# -V3.net
KiCad netlist of a schematic drawn in Altium Designer
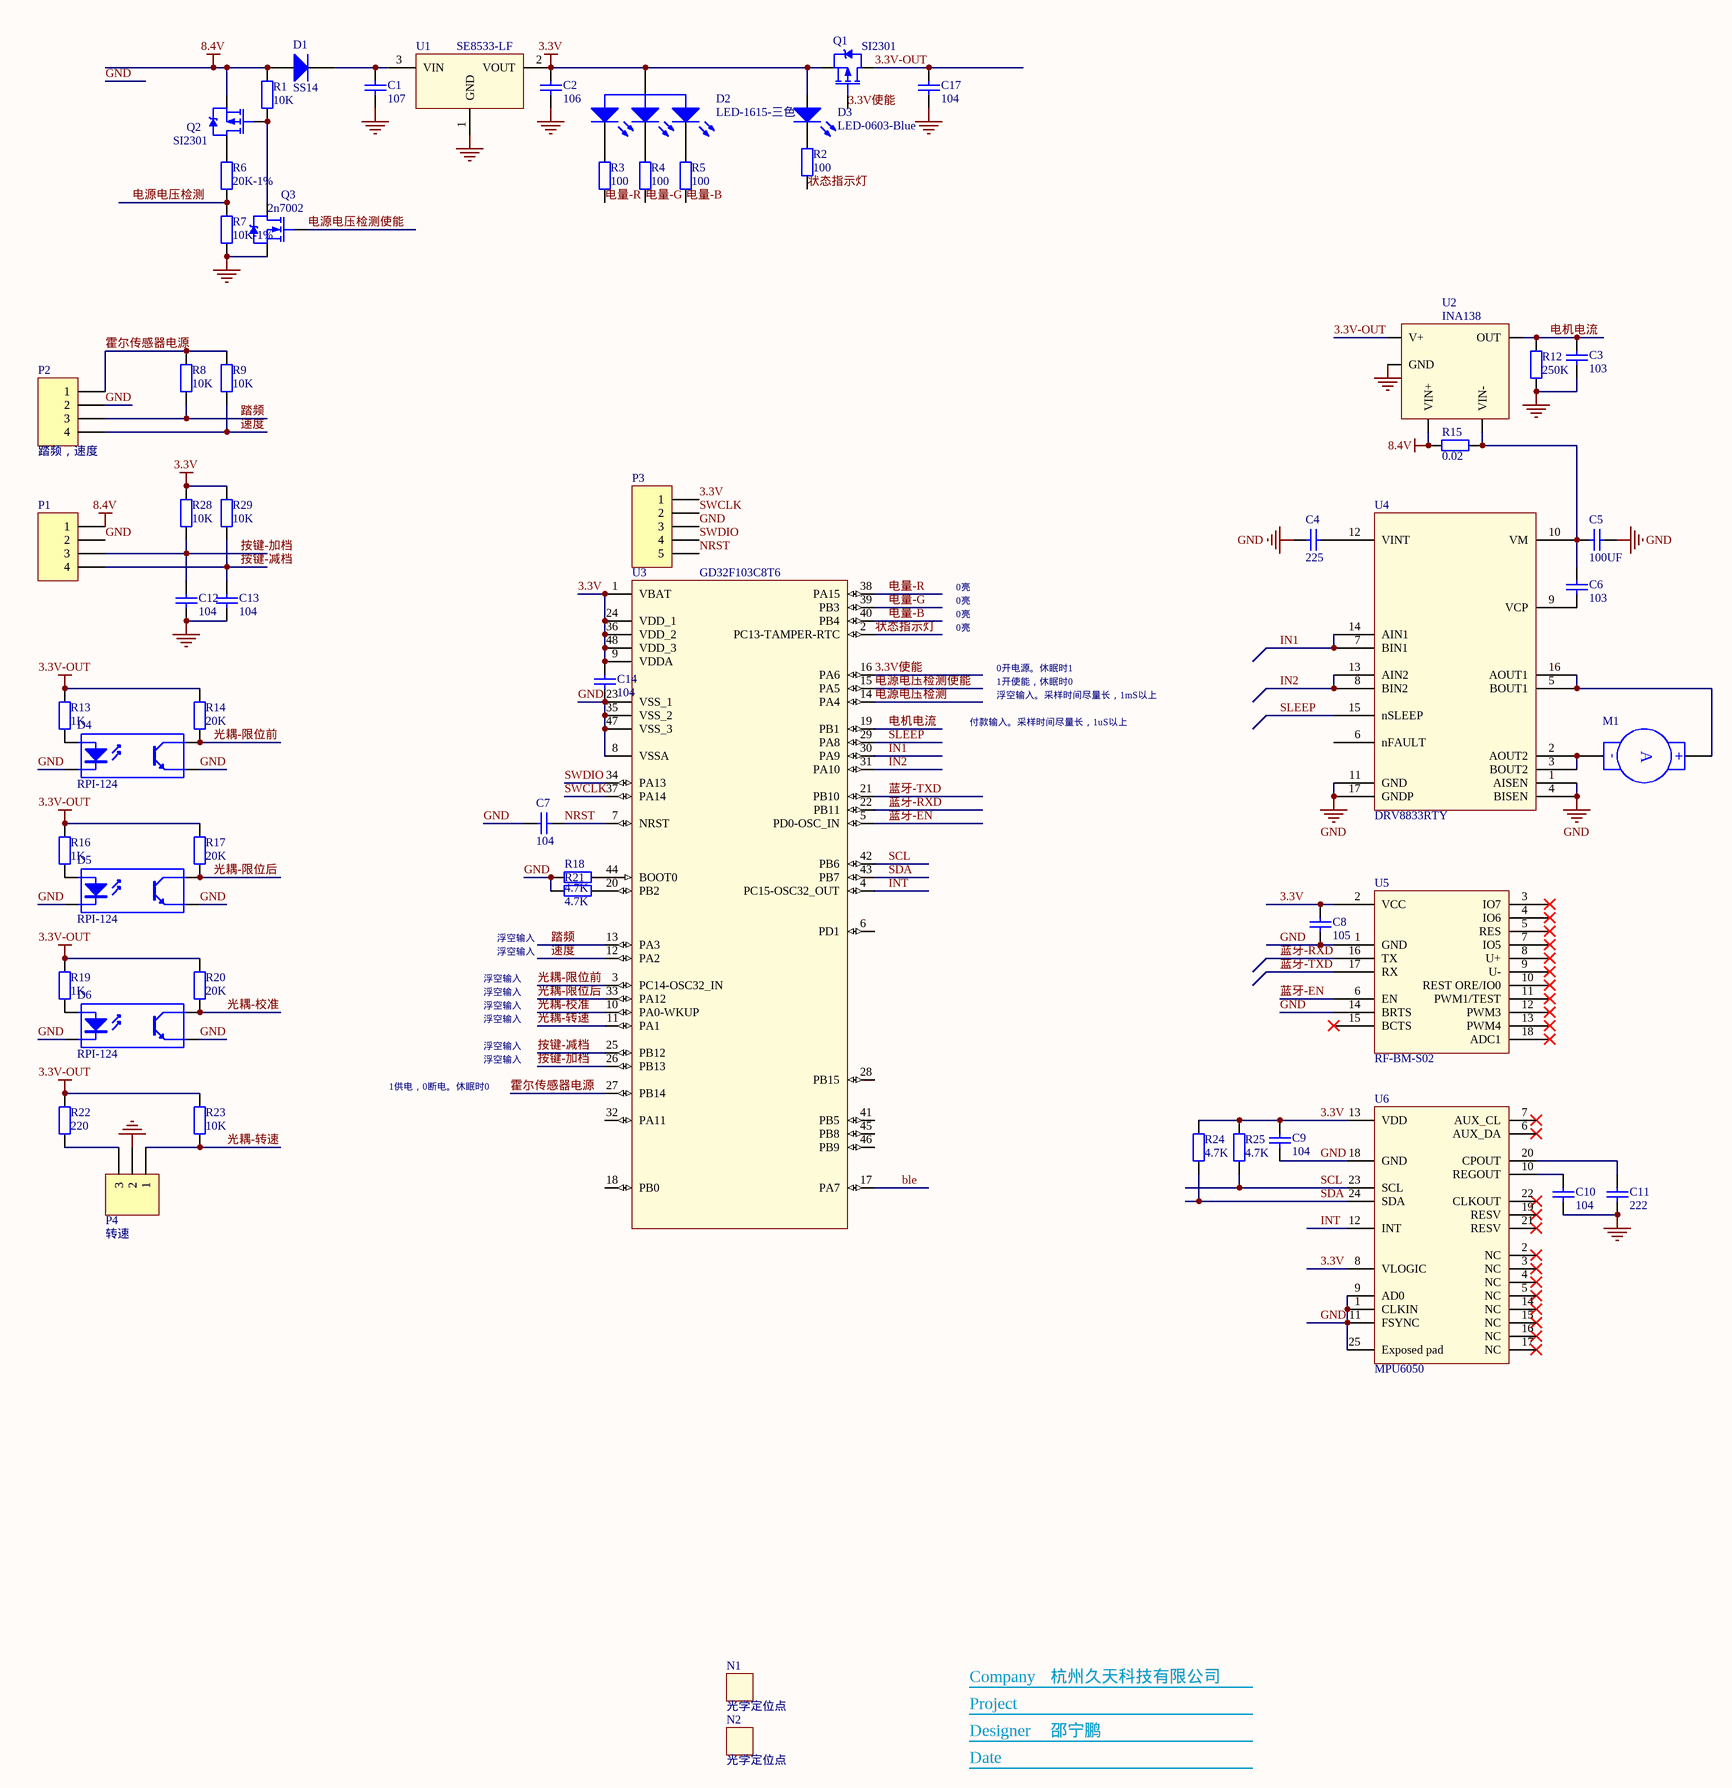
[diagram p0: 拉线式变速器-V3.SchDoc]

(export (version "E")
  (design (tool "Eeschema 10.0.6"))
  (components
    (comp (ref "C1")
      (value "107")
      (footprint "C-1206")
      (description "0805")
      (fields (field (name "PUBLISHER") "Altium Limited"))
      (libsource (lib "2电容-V1.0") (part "Cap-0603"))
    )
    (comp (ref "C2")
      (value "106")
      (footprint "C-0603-M")
      (description "0805")
      (fields (field (name "PUBLISHER") "Altium Limited"))
      (libsource (lib "2电容-V1.0") (part "Cap-0603"))
    )
    (comp (ref "C3")
      (value "103")
      (footprint "C-0603-M")
      (description "0805")
      (fields (field (name "PUBLISHER") "Altium Limited"))
      (libsource (lib "2电容-V1.0") (part "Cap-0603"))
    )
    (comp (ref "C4")
      (value "225")
      (footprint "C-0603-M")
      (description "0805")
      (fields (field (name "PUBLISHER") "Altium Limited"))
      (libsource (lib "2电容-V1.0") (part "Cap-0603"))
    )
    (comp (ref "C5")
      (value "100UF")
      (footprint "C-1206-M")
      (description "0805")
      (fields (field (name "PUBLISHER") "Altium Limited"))
      (libsource (lib "2电容-V1.0") (part "Cap-0805"))
    )
    (comp (ref "C6")
      (value "103")
      (footprint "C-0603-M")
      (description "0805")
      (fields (field (name "PUBLISHER") "Altium Limited"))
      (libsource (lib "2电容-V1.0") (part "Cap-0603"))
    )
    (comp (ref "C7")
      (value "104")
      (footprint "C-0603-M")
      (description "0805")
      (fields (field (name "PUBLISHER") "Altium Limited"))
      (libsource (lib "2电容-V1.0") (part "Cap-0603"))
    )
    (comp (ref "C8")
      (value "105")
      (footprint "C-0603-M")
      (description "0805")
      (fields (field (name "PUBLISHER") "Altium Limited"))
      (libsource (lib "2电容-V1.0") (part "Cap"))
    )
    (comp (ref "C9")
      (value "104")
      (footprint "C-0603-m")
      (description "0805")
      (fields (field (name "PUBLISHER") "Altium Limited"))
      (libsource (lib "2电容-V1.0") (part "Cap-0603"))
    )
    (comp (ref "C10")
      (value "104")
      (footprint "C-0603-m")
      (description "0805")
      (fields (field (name "PUBLISHER") "Altium Limited"))
      (libsource (lib "2电容-V1.0") (part "Cap-0603"))
    )
    (comp (ref "C11")
      (value "222")
      (footprint "C-0603-m")
      (description "0805")
      (fields (field (name "PUBLISHER") "Altium Limited"))
      (libsource (lib "2电容-V1.0") (part "Cap-0603"))
    )
    (comp (ref "C12")
      (value "104")
      (footprint "C-0603-M")
      (description "0805")
      (fields (field (name "PUBLISHER") "Altium Limited"))
      (libsource (lib "2电容-V1.0") (part "Cap-0603"))
    )
    (comp (ref "C13")
      (value "104")
      (footprint "C-0603-M")
      (description "0805")
      (fields (field (name "PUBLISHER") "Altium Limited"))
      (libsource (lib "2电容-V1.0") (part "Cap-0603"))
    )
    (comp (ref "C14")
      (value "104")
      (footprint "C-0603-M")
      (description "0805")
      (fields (field (name "PUBLISHER") "Altium Limited"))
      (libsource (lib "2电容-V1.0") (part "Cap-0603"))
    )
    (comp (ref "C17")
      (value "104")
      (footprint "C-0603-M")
      (description "0805")
      (fields (field (name "PUBLISHER") "Altium Limited"))
      (libsource (lib "2电容-V1.0") (part "Cap-0603"))
    )
    (comp (ref "D1")
      (value "SS14")
      (footprint "D-0603-M")
      (description "SMA")
      (libsource (lib "4二极管-V1.0") (part "SS14"))
    )
    (comp (ref "D2")
      (value "LED-1615-三色")
      (footprint "LED-1615-三色")
      (libsource (lib "4二极管-V1.1") (part "LED-1615-三色"))
    )
    (comp (ref "D3")
      (value "LED-0603-Blue")
      (footprint "LED-0603-Blue")
      (fields (field (name "PUBLISHER") "Altium Limited"))
      (libsource (lib "4二极管-V1.1") (part "LED-0603-Blue"))
    )
    (comp (ref "D4")
      (value "RPI-124")
      (footprint "RPI-124")
      (description "光电")
      (libsource (lib "4二极管-V11") (part "GP1S21"))
    )
    (comp (ref "D5")
      (value "RPI-124")
      (footprint "RPI-124")
      (description "光电")
      (libsource (lib "4二极管-V11") (part "GP1S21"))
    )
    (comp (ref "D6")
      (value "RPI-124")
      (footprint "RPI-124")
      (description "光电")
      (libsource (lib "4二极管-V11") (part "GP1S21"))
    )
    (comp (ref "M1")
      (value "~")
      (footprint "ZH1.5-2P-插件-直针")
      (description "直流电机")
      (fields (field (name "PUBLISHER") "Altium Limited"))
      (libsource (lib "3电感-V1.0") (part "Motor Servo"))
    )
    (comp (ref "N1") (value "光学定位点") (footprint "MARK-1mm-3mm") (libsource (lib "11其他元件-V1.0") (part "无引脚")))
    (comp (ref "N2") (value "光学定位点") (footprint "MARK-1mm-3mm") (libsource (lib "11其他元件-V1.0") (part "无引脚")))
    (comp (ref "P1")
      (value "~")
      (footprint "ZH1.5-4P-插件-直针")
      (description "Header, 4-Pin")
      (fields (field (name "PUBLISHER") "Altium Limited"))
      (libsource (lib "5排针-V1.0") (part "Header 4"))
    )
    (comp (ref "P2")
      (value "踏频，速度")
      (footprint "ZH1.5-4P-插件-直针")
      (description "Header, 4-Pin")
      (fields (field (name "PUBLISHER") "Altium Limited"))
      (libsource (lib "5排针-V1.0") (part "Header 4"))
    )
    (comp (ref "P3")
      (value "~")
      (footprint "5P下载口")
      (description "Header, 5-Pin")
      (fields (field (name "PUBLISHER") "Altium Limited"))
      (libsource (lib "5排针-V1.0") (part "Header 5"))
    )
    (comp (ref "P4")
      (value "转速")
      (footprint "ZH1.5-3P-插件-直针")
      (description "Header, 3-Pin")
      (fields (field (name "PUBLISHER") "Altium Limited"))
      (libsource (lib "5排针-V1.0") (part "Header 3"))
    )
    (comp (ref "Q1")
      (value "SI2301")
      (footprint "SOT-23")
      (description "SOT-23")
      (libsource (lib "4二极管-V1.1") (part "SI2301"))
    )
    (comp (ref "Q2")
      (value "SI2301")
      (footprint "SOT-23")
      (description "SOT-23")
      (libsource (lib "4二极管-V1.1") (part "SI2301"))
    )
    (comp (ref "Q3")
      (value "2n7002")
      (footprint "SOT-23")
      (description "SOT-23")
      (libsource (lib "4二极管-V1.1") (part "SI2300"))
    )
    (comp (ref "R1")
      (value "10K")
      (footprint "R-0603-M")
      (description "0603")
      (fields (field (name "PUBLISHER") "Altium Limited"))
      (libsource (lib "") (part "Res2-0603_2"))
    )
    (comp (ref "R2")
      (value "100")
      (footprint "R-0603-M")
      (description "0603")
      (fields (field (name "PUBLISHER") "Altium Limited"))
      (libsource (lib "1电阻-V1.0") (part "Res2-0603"))
    )
    (comp (ref "R3")
      (value "100")
      (footprint "R-0603-M")
      (description "0603")
      (fields (field (name "PUBLISHER") "Altium Limited"))
      (libsource (lib "1电阻-V1.0") (part "Res2-0603"))
    )
    (comp (ref "R4")
      (value "100")
      (footprint "R-0603-M")
      (description "0603")
      (fields (field (name "PUBLISHER") "Altium Limited"))
      (libsource (lib "1电阻-V1.0") (part "Res2-0603"))
    )
    (comp (ref "R5")
      (value "100")
      (footprint "R-0603-M")
      (description "0603")
      (fields (field (name "PUBLISHER") "Altium Limited"))
      (libsource (lib "1电阻-V1.0") (part "Res2-0603"))
    )
    (comp (ref "R6")
      (value "20K-1%")
      (footprint "R-0603-M")
      (description "0603")
      (fields (field (name "PUBLISHER") "Altium Limited"))
      (libsource (lib "") (part "Res2-0603_2"))
    )
    (comp (ref "R7")
      (value "10K-1%")
      (footprint "R-0603-M")
      (description "0603")
      (fields (field (name "PUBLISHER") "Altium Limited"))
      (libsource (lib "") (part "Res2-0603_2"))
    )
    (comp (ref "R8")
      (value "10K")
      (footprint "R-0603-m")
      (description "0603")
      (fields (field (name "PUBLISHER") "Altium Limited"))
      (libsource (lib "1电阻-V1.0") (part "Res2-0603-"))
    )
    (comp (ref "R9")
      (value "10K")
      (footprint "R-0603-m")
      (description "0603")
      (fields (field (name "PUBLISHER") "Altium Limited"))
      (libsource (lib "1电阻-V1.0") (part "Res2-0603-"))
    )
    (comp (ref "R12")
      (value "250K")
      (footprint "R-0603-m")
      (description "0603")
      (fields (field (name "PUBLISHER") "Altium Limited"))
      (libsource (lib "1电阻-V1.0") (part "Res2-0603"))
    )
    (comp (ref "R13")
      (value "1K")
      (footprint "R-0603-m")
      (description "0603")
      (fields (field (name "PUBLISHER") "Altium Limited"))
      (libsource (lib "1电阻-V1.0") (part "Res2-0603"))
    )
    (comp (ref "R14")
      (value "20K")
      (footprint "R-0603-m")
      (description "0603")
      (fields (field (name "PUBLISHER") "Altium Limited"))
      (libsource (lib "1电阻-V1.0") (part "Res2-0603"))
    )
    (comp (ref "R15")
      (value "0.02")
      (footprint "R-0603-m")
      (description "0603")
      (fields (field (name "PUBLISHER") "Altium Limited"))
      (libsource (lib "") (part "Res2-0603_1"))
    )
    (comp (ref "R16")
      (value "1K")
      (footprint "R-0603-m")
      (description "0603")
      (fields (field (name "PUBLISHER") "Altium Limited"))
      (libsource (lib "1电阻-V1.0") (part "Res2-0603"))
    )
    (comp (ref "R17")
      (value "20K")
      (footprint "R-0603-m")
      (description "0603")
      (fields (field (name "PUBLISHER") "Altium Limited"))
      (libsource (lib "1电阻-V1.0") (part "Res2-0603"))
    )
    (comp (ref "R18")
      (value "4.7K")
      (footprint "R-0603-m")
      (description "0603")
      (fields (field (name "PUBLISHER") "Altium Limited"))
      (libsource (lib "") (part "Res2-0603_1"))
    )
    (comp (ref "R19")
      (value "1K")
      (footprint "R-0603-m")
      (description "0603")
      (fields (field (name "PUBLISHER") "Altium Limited"))
      (libsource (lib "1电阻-V1.0") (part "Res2-0603"))
    )
    (comp (ref "R20")
      (value "20K")
      (footprint "R-0603-m")
      (description "0603")
      (fields (field (name "PUBLISHER") "Altium Limited"))
      (libsource (lib "1电阻-V1.0") (part "Res2-0603"))
    )
    (comp (ref "R21")
      (value "4.7K")
      (footprint "R-0603-m")
      (description "0603")
      (fields (field (name "PUBLISHER") "Altium Limited"))
      (libsource (lib "") (part "Res2-0603_1"))
    )
    (comp (ref "R22")
      (value "220")
      (footprint "R-0603-m")
      (description "0603")
      (fields (field (name "PUBLISHER") "Altium Limited"))
      (libsource (lib "1电阻-V1.0") (part "Res2-0603"))
    )
    (comp (ref "R23")
      (value "10K")
      (footprint "R-0603-m")
      (description "0603")
      (fields (field (name "PUBLISHER") "Altium Limited"))
      (libsource (lib "1电阻-V1.0") (part "Res2-0603"))
    )
    (comp (ref "R24")
      (value "4.7K")
      (footprint "R-0603-M")
      (description "0603")
      (fields (field (name "PUBLISHER") "Altium Limited"))
      (libsource (lib "") (part "Res2-0603-_1"))
    )
    (comp (ref "R25")
      (value "4.7K")
      (footprint "R-0603-M")
      (description "0603")
      (fields (field (name "PUBLISHER") "Altium Limited"))
      (libsource (lib "") (part "Res2-0603-_1"))
    )
    (comp (ref "R28")
      (value "10K")
      (footprint "R-0603-m")
      (description "0603")
      (fields (field (name "PUBLISHER") "Altium Limited"))
      (libsource (lib "1电阻-V1.0") (part "Res2-0603-"))
    )
    (comp (ref "R29")
      (value "10K")
      (footprint "R-0603-m")
      (description "0603")
      (fields (field (name "PUBLISHER") "Altium Limited"))
      (libsource (lib "1电阻-V1.0") (part "Res2-0603-"))
    )
    (comp (ref "U1")
      (value "SE8533-LF")
      (footprint "SOT-23")
      (libsource (lib "电源芯片-线性稳压-V1") (part "SE8533-LF"))
    )
    (comp (ref "U2") (value "INA138") (footprint "SOT-23-5-N") (libsource (lib "放大器和线性器件") (part "INA138")))
    (comp (ref "U3")
      (value "GD32F103C8T6")
      (footprint "LQFP48-L")
      (libsource (lib "9单片机-V1.0") (part "GD32F103C8T6"))
    )
    (comp (ref "U4")
      (value "DRV8833RTY")
      (footprint "QFN-16+1")
      (description "刷式电机驱动芯片")
      (libsource (lib "8集成电路-V11") (part "DRV8833RTY"))
    )
    (comp (ref "U5")
      (value "RF-BM-S02")
      (footprint "RF-BM-S02")
      (libsource (lib "6电路模块-V1.0") (part "RF-BM-S02"))
    )
    (comp (ref "U6")
      (value "MPU6050")
      (footprint "QFN-24")
      (description "三轴陀螺仪加速度传感器")
      (libsource (lib "8集成电路-V1.1") (part "MPU6050"))
    )
  )
  (nets
    (net (code "1") (name "/3.3V使能") (class "Default")
      (node (ref "Q1") (pin "1") (pinfunction "G_1") (pintype "passive"))
      (node (ref "U3") (pin "16") (pinfunction "PA6_16") (pintype "bidirectional"))
    )
    (net (code "2") (name "/IN1") (class "Default")
      (node (ref "U3") (pin "30") (pinfunction "PA9_30") (pintype "bidirectional"))
      (node (ref "U4") (pin "14") (pinfunction "AIN1_14") (pintype "passive"))
      (node (ref "U4") (pin "7") (pinfunction "BIN1_7") (pintype "passive"))
    )
    (net (code "3") (name "/IN2") (class "Default")
      (node (ref "U3") (pin "31") (pinfunction "PA10_31") (pintype "bidirectional"))
      (node (ref "U4") (pin "13") (pinfunction "AIN2_13") (pintype "passive"))
      (node (ref "U4") (pin "8") (pinfunction "BIN2_8") (pintype "passive"))
    )
    (net (code "4") (name "/INT") (class "Default")
      (node (ref "U3") (pin "4") (pinfunction "PC15-OSC32_OUT_4") (pintype "bidirectional"))
      (node (ref "U6") (pin "12") (pinfunction "INT_12") (pintype "passive"))
    )
    (net (code "5") (name "/NRST") (class "Default")
      (node (ref "C7") (pin "2") (pinfunction "2_2") (pintype "passive"))
      (node (ref "P3") (pin "5") (pinfunction "5_5") (pintype "passive"))
      (node (ref "U3") (pin "7") (pinfunction "NRST_7") (pintype "bidirectional"))
    )
    (net (code "6") (name "/SCL") (class "Default")
      (node (ref "R25") (pin "1") (pinfunction "1_1") (pintype "passive"))
      (node (ref "U3") (pin "42") (pinfunction "PB6_42") (pintype "bidirectional"))
      (node (ref "U6") (pin "23") (pinfunction "SCL_23") (pintype "passive"))
    )
    (net (code "7") (name "/SDA") (class "Default")
      (node (ref "R24") (pin "1") (pinfunction "1_1") (pintype "passive"))
      (node (ref "U3") (pin "43") (pinfunction "PB7_43") (pintype "bidirectional"))
      (node (ref "U6") (pin "24") (pinfunction "SDA_24") (pintype "passive"))
    )
    (net (code "8") (name "/SLEEP") (class "Default")
      (node (ref "U3") (pin "29") (pinfunction "PA8_29") (pintype "bidirectional"))
      (node (ref "U4") (pin "15") (pinfunction "nSLEEP_15") (pintype "passive"))
    )
    (net (code "9") (name "/SWCLK") (class "Default")
      (node (ref "P3") (pin "2") (pinfunction "2_2") (pintype "passive"))
      (node (ref "U3") (pin "37") (pinfunction "PA14_37") (pintype "bidirectional"))
    )
    (net (code "10") (name "/SWDIO") (class "Default")
      (node (ref "P3") (pin "4") (pinfunction "4_4") (pintype "passive"))
      (node (ref "U3") (pin "34") (pinfunction "PA13_34") (pintype "bidirectional"))
    )
    (net (code "11") (name "/ble") (class "Default")
      (node (ref "U3") (pin "17") (pinfunction "PA7_17") (pintype "bidirectional"))
    )
    (net (code "12") (name "/光耦-校准") (class "Default")
      (node (ref "D6") (pin "4") (pinfunction "C_4") (pintype "passive"))
      (node (ref "R20") (pin "1") (pinfunction "1_1") (pintype "passive"))
      (node (ref "U3") (pin "10") (pinfunction "PA0-WKUP_10") (pintype "bidirectional"))
    )
    (net (code "13") (name "/光耦-转速") (class "Default")
      (node (ref "P4") (pin "1") (pinfunction "1_1") (pintype "passive"))
      (node (ref "R23") (pin "1") (pinfunction "1_1") (pintype "passive"))
      (node (ref "U3") (pin "11") (pinfunction "PA1_11") (pintype "bidirectional"))
    )
    (net (code "14") (name "/光耦-限位前") (class "Default")
      (node (ref "D4") (pin "4") (pinfunction "C_4") (pintype "passive"))
      (node (ref "R14") (pin "1") (pinfunction "1_1") (pintype "passive"))
      (node (ref "U3") (pin "3") (pinfunction "PC14-OSC32_IN_3") (pintype "bidirectional"))
    )
    (net (code "15") (name "/光耦-限位后") (class "Default")
      (node (ref "D5") (pin "4") (pinfunction "C_4") (pintype "passive"))
      (node (ref "R17") (pin "1") (pinfunction "1_1") (pintype "passive"))
      (node (ref "U3") (pin "33") (pinfunction "PA12_33") (pintype "bidirectional"))
    )
    (net (code "16") (name "/按键-减档") (class "Default")
      (node (ref "C13") (pin "2") (pinfunction "2_2") (pintype "passive"))
      (node (ref "P1") (pin "4") (pinfunction "4_4") (pintype "passive"))
      (node (ref "R29") (pin "2") (pinfunction "2_2") (pintype "passive"))
      (node (ref "U3") (pin "25") (pinfunction "PB12_25") (pintype "bidirectional"))
    )
    (net (code "17") (name "/按键-加档") (class "Default")
      (node (ref "C12") (pin "2") (pinfunction "2_2") (pintype "passive"))
      (node (ref "P1") (pin "3") (pinfunction "3_3") (pintype "passive"))
      (node (ref "R28") (pin "2") (pinfunction "2_2") (pintype "passive"))
      (node (ref "U3") (pin "26") (pinfunction "PB13_26") (pintype "bidirectional"))
    )
    (net (code "18") (name "/状态指示灯") (class "Default")
      (node (ref "R2") (pin "1") (pinfunction "1_1") (pintype "passive"))
      (node (ref "U3") (pin "2") (pinfunction "PC13-TAMPER-RTC_2") (pintype "bidirectional"))
    )
    (net (code "19") (name "/电机电流") (class "Default")
      (node (ref "C3") (pin "1") (pinfunction "1_1") (pintype "passive"))
      (node (ref "R12") (pin "2") (pinfunction "2_2") (pintype "passive"))
      (node (ref "U2") (pin "1") (pinfunction "OUT_1") (pintype "passive"))
      (node (ref "U3") (pin "19") (pinfunction "PB1_19") (pintype "bidirectional"))
    )
    (net (code "20") (name "/电源电压检测") (class "Default")
      (node (ref "R6") (pin "2") (pinfunction "2_2") (pintype "passive"))
      (node (ref "R7") (pin "1") (pinfunction "1_1") (pintype "passive"))
      (node (ref "U3") (pin "14") (pinfunction "PA4_14") (pintype "bidirectional"))
    )
    (net (code "21") (name "/电源电压检测使能") (class "Default")
      (node (ref "Q3") (pin "1") (pinfunction "G_1") (pintype "passive"))
      (node (ref "U3") (pin "15") (pinfunction "PA5_15") (pintype "bidirectional"))
    )
    (net (code "22") (name "/电量-B") (class "Default")
      (node (ref "R5") (pin "1") (pinfunction "1_1") (pintype "passive"))
      (node (ref "U3") (pin "40") (pinfunction "PB4_40") (pintype "bidirectional"))
    )
    (net (code "23") (name "/电量-G") (class "Default")
      (node (ref "R4") (pin "1") (pinfunction "1_1") (pintype "passive"))
      (node (ref "U3") (pin "39") (pinfunction "PB3_39") (pintype "bidirectional"))
    )
    (net (code "24") (name "/电量-R") (class "Default")
      (node (ref "R3") (pin "1") (pinfunction "1_1") (pintype "passive"))
      (node (ref "U3") (pin "38") (pinfunction "PA15_38") (pintype "bidirectional"))
    )
    (net (code "25") (name "/蓝牙-EN") (class "Default")
      (node (ref "U3") (pin "5") (pinfunction "PD0-OSC_IN_5") (pintype "bidirectional"))
      (node (ref "U5") (pin "6") (pinfunction "EN_6") (pintype "passive"))
    )
    (net (code "26") (name "/蓝牙-RXD") (class "Default")
      (node (ref "U3") (pin "22") (pinfunction "PB11_22") (pintype "bidirectional"))
      (node (ref "U5") (pin "16") (pinfunction "TX_16") (pintype "passive"))
    )
    (net (code "27") (name "/蓝牙-TXD") (class "Default")
      (node (ref "U3") (pin "21") (pinfunction "PB10_21") (pintype "bidirectional"))
      (node (ref "U5") (pin "17") (pinfunction "RX_17") (pintype "passive"))
    )
    (net (code "28") (name "/踏频") (class "Default")
      (node (ref "P2") (pin "3") (pinfunction "3_3") (pintype "passive"))
      (node (ref "R8") (pin "2") (pinfunction "2_2") (pintype "passive"))
      (node (ref "U3") (pin "13") (pinfunction "PA3_13") (pintype "bidirectional"))
    )
    (net (code "29") (name "/速度") (class "Default")
      (node (ref "P2") (pin "4") (pinfunction "4_4") (pintype "passive"))
      (node (ref "R9") (pin "2") (pinfunction "2_2") (pintype "passive"))
      (node (ref "U3") (pin "12") (pinfunction "PA2_12") (pintype "bidirectional"))
    )
    (net (code "30") (name "/霍尔传感器电源") (class "Default")
      (node (ref "P2") (pin "1") (pinfunction "1_1") (pintype "passive"))
      (node (ref "R8") (pin "1") (pinfunction "1_1") (pintype "passive"))
      (node (ref "R9") (pin "1") (pinfunction "1_1") (pintype "passive"))
      (node (ref "U3") (pin "27") (pinfunction "PB14_27") (pintype "bidirectional"))
    )
    (net (code "31") (name "3.3V") (class "Default")
      (node (ref "C14") (pin "1") (pinfunction "1_1") (pintype "passive"))
      (node (ref "C2") (pin "2") (pinfunction "2_2") (pintype "passive"))
      (node (ref "C8") (pin "1") (pinfunction "1_1") (pintype "passive"))
      (node (ref "C9") (pin "1") (pinfunction "1_1") (pintype "passive"))
      (node (ref "D2") (pin "2") (pinfunction "A_2") (pintype "passive"))
      (node (ref "D3") (pin "1") (pinfunction "A_1") (pintype "passive"))
      (node (ref "P3") (pin "1") (pinfunction "1_1") (pintype "passive"))
      (node (ref "Q1") (pin "2") (pinfunction "S_2") (pintype "passive"))
      (node (ref "R24") (pin "2") (pinfunction "2_2") (pintype "passive"))
      (node (ref "R25") (pin "2") (pinfunction "2_2") (pintype "passive"))
      (node (ref "R28") (pin "1") (pinfunction "1_1") (pintype "passive"))
      (node (ref "R29") (pin "1") (pinfunction "1_1") (pintype "passive"))
      (node (ref "U1") (pin "2") (pinfunction "VOUT_2") (pintype "passive"))
      (node (ref "U3") (pin "1") (pinfunction "VBAT_1") (pintype "power_in"))
      (node (ref "U3") (pin "24") (pinfunction "VDD_1_24") (pintype "power_in"))
      (node (ref "U3") (pin "36") (pinfunction "VDD_2_36") (pintype "power_in"))
      (node (ref "U3") (pin "48") (pinfunction "VDD_3_48") (pintype "power_in"))
      (node (ref "U3") (pin "9") (pinfunction "VDDA_9") (pintype "power_in"))
      (node (ref "U5") (pin "2") (pinfunction "VCC_2") (pintype "passive"))
      (node (ref "U6") (pin "13") (pinfunction "VDD_13") (pintype "passive"))
      (node (ref "U6") (pin "8") (pinfunction "VLOGIC_8") (pintype "passive"))
    )
    (net (code "32") (name "3.3V-OUT") (class "Default")
      (node (ref "C17") (pin "1") (pinfunction "1_1") (pintype "passive"))
      (node (ref "Q1") (pin "3") (pinfunction "D_3") (pintype "passive"))
      (node (ref "R13") (pin "2") (pinfunction "2_2") (pintype "passive"))
      (node (ref "R14") (pin "2") (pinfunction "2_2") (pintype "passive"))
      (node (ref "R16") (pin "2") (pinfunction "2_2") (pintype "passive"))
      (node (ref "R17") (pin "2") (pinfunction "2_2") (pintype "passive"))
      (node (ref "R19") (pin "2") (pinfunction "2_2") (pintype "passive"))
      (node (ref "R20") (pin "2") (pinfunction "2_2") (pintype "passive"))
      (node (ref "R22") (pin "2") (pinfunction "2_2") (pintype "passive"))
      (node (ref "R23") (pin "2") (pinfunction "2_2") (pintype "passive"))
      (node (ref "U2") (pin "5") (pinfunction "V+_5") (pintype "passive"))
    )
    (net (code "33") (name "8.4V") (class "Default")
      (node (ref "D1") (pin "1") (pinfunction "A_1") (pintype "passive"))
      (node (ref "P1") (pin "1") (pinfunction "1_1") (pintype "passive"))
      (node (ref "Q2") (pin "2") (pinfunction "S_2") (pintype "passive"))
      (node (ref "R1") (pin "1") (pinfunction "1_1") (pintype "passive"))
      (node (ref "R15") (pin "2") (pinfunction "2_2") (pintype "passive"))
      (node (ref "U2") (pin "3") (pinfunction "VIN+_3") (pintype "passive"))
    )
    (net (code "34") (name "GND") (class "Default")
      (node (ref "C1") (pin "1") (pinfunction "1_1") (pintype "passive"))
      (node (ref "C10") (pin "2") (pinfunction "2_2") (pintype "passive"))
      (node (ref "C11") (pin "2") (pinfunction "2_2") (pintype "passive"))
      (node (ref "C12") (pin "1") (pinfunction "1_1") (pintype "passive"))
      (node (ref "C13") (pin "1") (pinfunction "1_1") (pintype "passive"))
      (node (ref "C14") (pin "2") (pinfunction "2_2") (pintype "passive"))
      (node (ref "C17") (pin "2") (pinfunction "2_2") (pintype "passive"))
      (node (ref "C2") (pin "1") (pinfunction "1_1") (pintype "passive"))
      (node (ref "C3") (pin "2") (pinfunction "2_2") (pintype "passive"))
      (node (ref "C4") (pin "1") (pinfunction "1_1") (pintype "passive"))
      (node (ref "C5") (pin "1") (pinfunction "1_1") (pintype "passive"))
      (node (ref "C7") (pin "1") (pinfunction "1_1") (pintype "passive"))
      (node (ref "C8") (pin "2") (pinfunction "2_2") (pintype "passive"))
      (node (ref "C9") (pin "2") (pinfunction "2_2") (pintype "passive"))
      (node (ref "D4") (pin "2") (pinfunction "K_2") (pintype "passive"))
      (node (ref "D4") (pin "3") (pinfunction "E_3") (pintype "passive"))
      (node (ref "D5") (pin "2") (pinfunction "K_2") (pintype "passive"))
      (node (ref "D5") (pin "3") (pinfunction "E_3") (pintype "passive"))
      (node (ref "D6") (pin "2") (pinfunction "K_2") (pintype "passive"))
      (node (ref "D6") (pin "3") (pinfunction "E_3") (pintype "passive"))
      (node (ref "P1") (pin "2") (pinfunction "2_2") (pintype "passive"))
      (node (ref "P2") (pin "2") (pinfunction "2_2") (pintype "passive"))
      (node (ref "P3") (pin "3") (pinfunction "3_3") (pintype "passive"))
      (node (ref "P4") (pin "2") (pinfunction "2_2") (pintype "passive"))
      (node (ref "Q3") (pin "2") (pinfunction "S_2") (pintype "passive"))
      (node (ref "R12") (pin "1") (pinfunction "1_1") (pintype "passive"))
      (node (ref "R18") (pin "2") (pinfunction "2_2") (pintype "passive"))
      (node (ref "R21") (pin "2") (pinfunction "2_2") (pintype "passive"))
      (node (ref "R7") (pin "2") (pinfunction "2_2") (pintype "passive"))
      (node (ref "U1") (pin "1") (pinfunction "GND_1") (pintype "passive"))
      (node (ref "U2") (pin "2") (pinfunction "GND_2") (pintype "passive"))
      (node (ref "U3") (pin "23") (pinfunction "VSS_1_23") (pintype "power_in"))
      (node (ref "U3") (pin "35") (pinfunction "VSS_2_35") (pintype "power_in"))
      (node (ref "U3") (pin "47") (pinfunction "VSS_3_47") (pintype "power_in"))
      (node (ref "U3") (pin "8") (pinfunction "VSSA_8") (pintype "power_in"))
      (node (ref "U4") (pin "1") (pinfunction "AISEN_1") (pintype "passive"))
      (node (ref "U4") (pin "11") (pinfunction "GND_11") (pintype "passive"))
      (node (ref "U4") (pin "17") (pinfunction "GNDP_17") (pintype "passive"))
      (node (ref "U4") (pin "4") (pinfunction "BISEN_4") (pintype "passive"))
      (node (ref "U5") (pin "1") (pinfunction "GND_1") (pintype "passive"))
      (node (ref "U5") (pin "14") (pinfunction "BRTS_14") (pintype "passive"))
      (node (ref "U6") (pin "1") (pinfunction "CLKIN_1") (pintype "passive"))
      (node (ref "U6") (pin "11") (pinfunction "FSYNC_11") (pintype "passive"))
      (node (ref "U6") (pin "18") (pinfunction "GND_18") (pintype "passive"))
      (node (ref "U6") (pin "25") (pinfunction "Exposed_pad_25") (pintype "passive"))
      (node (ref "U6") (pin "9") (pinfunction "AD0_9") (pintype "passive"))
    )
    (net (code "35") (name "Net-(D1-K)") (class "Default")
      (node (ref "C1") (pin "2") (pinfunction "2_2") (pintype "passive"))
      (node (ref "D1") (pin "2") (pinfunction "K_2") (pintype "passive"))
      (node (ref "U1") (pin "3") (pinfunction "VIN_3") (pintype "passive"))
    )
    (net (code "36") (name "Net-(D2-B)") (class "Default")
      (node (ref "D2") (pin "3") (pinfunction "B_3") (pintype "passive"))
      (node (ref "R5") (pin "2") (pinfunction "2_2") (pintype "passive"))
    )
    (net (code "37") (name "Net-(D2-G)") (class "Default")
      (node (ref "D2") (pin "4") (pinfunction "G_4") (pintype "passive"))
      (node (ref "R4") (pin "2") (pinfunction "2_2") (pintype "passive"))
    )
    (net (code "38") (name "Net-(D2-R)") (class "Default")
      (node (ref "D2") (pin "1") (pinfunction "R_1") (pintype "passive"))
      (node (ref "R3") (pin "2") (pinfunction "2_2") (pintype "passive"))
    )
    (net (code "39") (name "Net-(D3-K)") (class "Default")
      (node (ref "D3") (pin "2") (pinfunction "K_2") (pintype "passive"))
      (node (ref "R2") (pin "2") (pinfunction "2_2") (pintype "passive"))
    )
    (net (code "40") (name "Net-(D4-A)") (class "Default")
      (node (ref "D4") (pin "1") (pinfunction "A_1") (pintype "passive"))
      (node (ref "R13") (pin "1") (pinfunction "1_1") (pintype "passive"))
    )
    (net (code "41") (name "Net-(D5-A)") (class "Default")
      (node (ref "D5") (pin "1") (pinfunction "A_1") (pintype "passive"))
      (node (ref "R16") (pin "1") (pinfunction "1_1") (pintype "passive"))
    )
    (net (code "42") (name "Net-(D6-A)") (class "Default")
      (node (ref "D6") (pin "1") (pinfunction "A_1") (pintype "passive"))
      (node (ref "R19") (pin "1") (pinfunction "1_1") (pintype "passive"))
    )
    (net (code "43") (name "Net-(M1-+)") (class "Default")
      (node (ref "M1") (pin "1") (pinfunction "+_1") (pintype "passive"))
      (node (ref "U4") (pin "16") (pinfunction "AOUT1_16") (pintype "passive"))
      (node (ref "U4") (pin "5") (pinfunction "BOUT1_5") (pintype "passive"))
    )
    (net (code "44") (name "Net-(M1--)") (class "Default")
      (node (ref "M1") (pin "2") (pinfunction "-_2") (pintype "passive"))
      (node (ref "U4") (pin "2") (pinfunction "AOUT2_2") (pintype "passive"))
      (node (ref "U4") (pin "3") (pinfunction "BOUT2_3") (pintype "passive"))
    )
    (net (code "45") (name "Net-(P4-Pad3)") (class "Default")
      (node (ref "P4") (pin "3") (pinfunction "3_3") (pintype "passive"))
      (node (ref "R22") (pin "1") (pinfunction "1_1") (pintype "passive"))
    )
    (net (code "46") (name "Net-(Q2-D)") (class "Default")
      (node (ref "Q2") (pin "3") (pinfunction "D_3") (pintype "passive"))
      (node (ref "R6") (pin "1") (pinfunction "1_1") (pintype "passive"))
    )
    (net (code "47") (name "Net-(Q2-G)") (class "Default")
      (node (ref "Q2") (pin "1") (pinfunction "G_1") (pintype "passive"))
      (node (ref "Q3") (pin "3") (pinfunction "D_3") (pintype "passive"))
      (node (ref "R1") (pin "2") (pinfunction "2_2") (pintype "passive"))
    )
    (net (code "48") (name "Net-(U2-VIN-)") (class "Default")
      (node (ref "C5") (pin "2") (pinfunction "2_2") (pintype "passive"))
      (node (ref "C6") (pin "1") (pinfunction "1_1") (pintype "passive"))
      (node (ref "R15") (pin "1") (pinfunction "1_1") (pintype "passive"))
      (node (ref "U2") (pin "4") (pinfunction "VIN-_4") (pintype "passive"))
      (node (ref "U4") (pin "10") (pinfunction "VM_10") (pintype "passive"))
    )
    (net (code "49") (name "Net-(U3-BOOT0)") (class "Default")
      (node (ref "R18") (pin "1") (pinfunction "1_1") (pintype "passive"))
      (node (ref "U3") (pin "44") (pinfunction "BOOT0_44") (pintype "input"))
    )
    (net (code "50") (name "Net-(U3-PB2)") (class "Default")
      (node (ref "R21") (pin "1") (pinfunction "1_1") (pintype "passive"))
      (node (ref "U3") (pin "20") (pinfunction "PB2_20") (pintype "bidirectional"))
    )
    (net (code "51") (name "Net-(U4-VCP)") (class "Default")
      (node (ref "C6") (pin "2") (pinfunction "2_2") (pintype "passive"))
      (node (ref "U4") (pin "9") (pinfunction "VCP_9") (pintype "passive"))
    )
    (net (code "52") (name "Net-(U4-VINT)") (class "Default")
      (node (ref "C4") (pin "2") (pinfunction "2_2") (pintype "passive"))
      (node (ref "U4") (pin "12") (pinfunction "VINT_12") (pintype "passive"))
    )
    (net (code "53") (name "Net-(U6-CPOUT)") (class "Default")
      (node (ref "C11") (pin "1") (pinfunction "1_1") (pintype "passive"))
      (node (ref "U6") (pin "20") (pinfunction "CPOUT_20") (pintype "passive"))
    )
    (net (code "54") (name "Net-(U6-REGOUT)") (class "Default")
      (node (ref "C10") (pin "1") (pinfunction "1_1") (pintype "passive"))
      (node (ref "U6") (pin "10") (pinfunction "REGOUT_10") (pintype "passive"))
    )
    (net (code "55") (name "unconnected-(U3-PA11-Pad32)") (class "Default")
      (node (ref "U3") (pin "32") (pinfunction "PA11_32") (pintype "bidirectional"))
    )
    (net (code "56") (name "unconnected-(U3-PB0-Pad18)") (class "Default")
      (node (ref "U3") (pin "18") (pinfunction "PB0_18") (pintype "bidirectional"))
    )
    (net (code "57") (name "unconnected-(U3-PB5-Pad41)") (class "Default")
      (node (ref "U3") (pin "41") (pinfunction "PB5_41") (pintype "bidirectional"))
    )
    (net (code "58") (name "unconnected-(U3-PB8-Pad45)") (class "Default")
      (node (ref "U3") (pin "45") (pinfunction "PB8_45") (pintype "bidirectional"))
    )
    (net (code "59") (name "unconnected-(U3-PB9-Pad46)") (class "Default")
      (node (ref "U3") (pin "46") (pinfunction "PB9_46") (pintype "bidirectional"))
    )
    (net (code "60") (name "unconnected-(U3-PB15-Pad28)") (class "Default")
      (node (ref "U3") (pin "28") (pinfunction "PB15_28") (pintype "bidirectional"))
    )
    (net (code "61") (name "unconnected-(U3-PD1-Pad6)") (class "Default")
      (node (ref "U3") (pin "6") (pinfunction "PD1_6") (pintype "bidirectional"))
    )
    (net (code "62") (name "unconnected-(U4-nFAULT-Pad6)") (class "Default")
      (node (ref "U4") (pin "6") (pinfunction "nFAULT_6") (pintype "passive"))
    )
    (net (code "63") (name "unconnected-(U5-ADC1-Pad18)") (class "Default")
      (node (ref "U5") (pin "18") (pinfunction "ADC1_18") (pintype "passive+no_connect"))
    )
    (net (code "64") (name "unconnected-(U5-BCTS-Pad15)") (class "Default")
      (node (ref "U5") (pin "15") (pinfunction "BCTS_15") (pintype "passive+no_connect"))
    )
    (net (code "65") (name "unconnected-(U5-IO5-Pad7)") (class "Default")
      (node (ref "U5") (pin "7") (pinfunction "IO5_7") (pintype "passive+no_connect"))
    )
    (net (code "66") (name "unconnected-(U5-IO6-Pad4)") (class "Default")
      (node (ref "U5") (pin "4") (pinfunction "IO6_4") (pintype "passive+no_connect"))
    )
    (net (code "67") (name "unconnected-(U5-IO7-Pad3)") (class "Default")
      (node (ref "U5") (pin "3") (pinfunction "IO7_3") (pintype "passive+no_connect"))
    )
    (net (code "68") (name "unconnected-(U5-PWM1{slash}TEST-Pad11)") (class "Default")
      (node (ref "U5") (pin "11") (pinfunction "PWM1/TEST_11") (pintype "passive+no_connect"))
    )
    (net (code "69") (name "unconnected-(U5-PWM3-Pad12)") (class "Default")
      (node (ref "U5") (pin "12") (pinfunction "PWM3_12") (pintype "passive+no_connect"))
    )
    (net (code "70") (name "unconnected-(U5-PWM4-Pad13)") (class "Default")
      (node (ref "U5") (pin "13") (pinfunction "PWM4_13") (pintype "passive+no_connect"))
    )
    (net (code "71") (name "unconnected-(U5-RES-Pad5)") (class "Default")
      (node (ref "U5") (pin "5") (pinfunction "RES_5") (pintype "passive+no_connect"))
    )
    (net (code "72") (name "unconnected-(U5-REST_ORE{slash}IO0-Pad10)") (class "Default")
      (node (ref "U5") (pin "10") (pinfunction "REST_ORE/IO0_10") (pintype "passive+no_connect"))
    )
    (net (code "73") (name "unconnected-(U5-U+-Pad8)") (class "Default")
      (node (ref "U5") (pin "8") (pinfunction "U+_8") (pintype "passive+no_connect"))
    )
    (net (code "74") (name "unconnected-(U5-U--Pad9)") (class "Default")
      (node (ref "U5") (pin "9") (pinfunction "U-_9") (pintype "passive+no_connect"))
    )
    (net (code "75") (name "unconnected-(U6-AUX_CL-Pad7)") (class "Default")
      (node (ref "U6") (pin "7") (pinfunction "AUX_CL_7") (pintype "passive+no_connect"))
    )
    (net (code "76") (name "unconnected-(U6-AUX_DA-Pad6)") (class "Default")
      (node (ref "U6") (pin "6") (pinfunction "AUX_DA_6") (pintype "passive+no_connect"))
    )
    (net (code "77") (name "unconnected-(U6-CLKOUT-Pad22)") (class "Default")
      (node (ref "U6") (pin "22") (pinfunction "CLKOUT_22") (pintype "passive+no_connect"))
    )
    (net (code "78") (name "unconnected-(U6-NC-Pad2)") (class "Default")
      (node (ref "U6") (pin "2") (pinfunction "NC_2") (pintype "passive+no_connect"))
    )
    (net (code "79") (name "unconnected-(U6-NC-Pad3)") (class "Default")
      (node (ref "U6") (pin "3") (pinfunction "NC_3") (pintype "passive+no_connect"))
    )
    (net (code "80") (name "unconnected-(U6-NC-Pad4)") (class "Default")
      (node (ref "U6") (pin "4") (pinfunction "NC_4") (pintype "passive+no_connect"))
    )
    (net (code "81") (name "unconnected-(U6-NC-Pad5)") (class "Default")
      (node (ref "U6") (pin "5") (pinfunction "NC_5") (pintype "passive+no_connect"))
    )
    (net (code "82") (name "unconnected-(U6-NC-Pad14)") (class "Default")
      (node (ref "U6") (pin "14") (pinfunction "NC_14") (pintype "passive+no_connect"))
    )
    (net (code "83") (name "unconnected-(U6-NC-Pad15)") (class "Default")
      (node (ref "U6") (pin "15") (pinfunction "NC_15") (pintype "passive+no_connect"))
    )
    (net (code "84") (name "unconnected-(U6-NC-Pad16)") (class "Default")
      (node (ref "U6") (pin "16") (pinfunction "NC_16") (pintype "passive+no_connect"))
    )
    (net (code "85") (name "unconnected-(U6-NC-Pad17)") (class "Default")
      (node (ref "U6") (pin "17") (pinfunction "NC_17") (pintype "passive+no_connect"))
    )
    (net (code "86") (name "unconnected-(U6-RESV-Pad19)") (class "Default")
      (node (ref "U6") (pin "19") (pinfunction "RESV_19") (pintype "passive+no_connect"))
    )
    (net (code "87") (name "unconnected-(U6-RESV-Pad21)") (class "Default")
      (node (ref "U6") (pin "21") (pinfunction "RESV_21") (pintype "passive+no_connect"))
    )
  )
)
